# STM32MP25XXAK_Power.net
KiCad netlist of a schematic drawn in Altium Designer
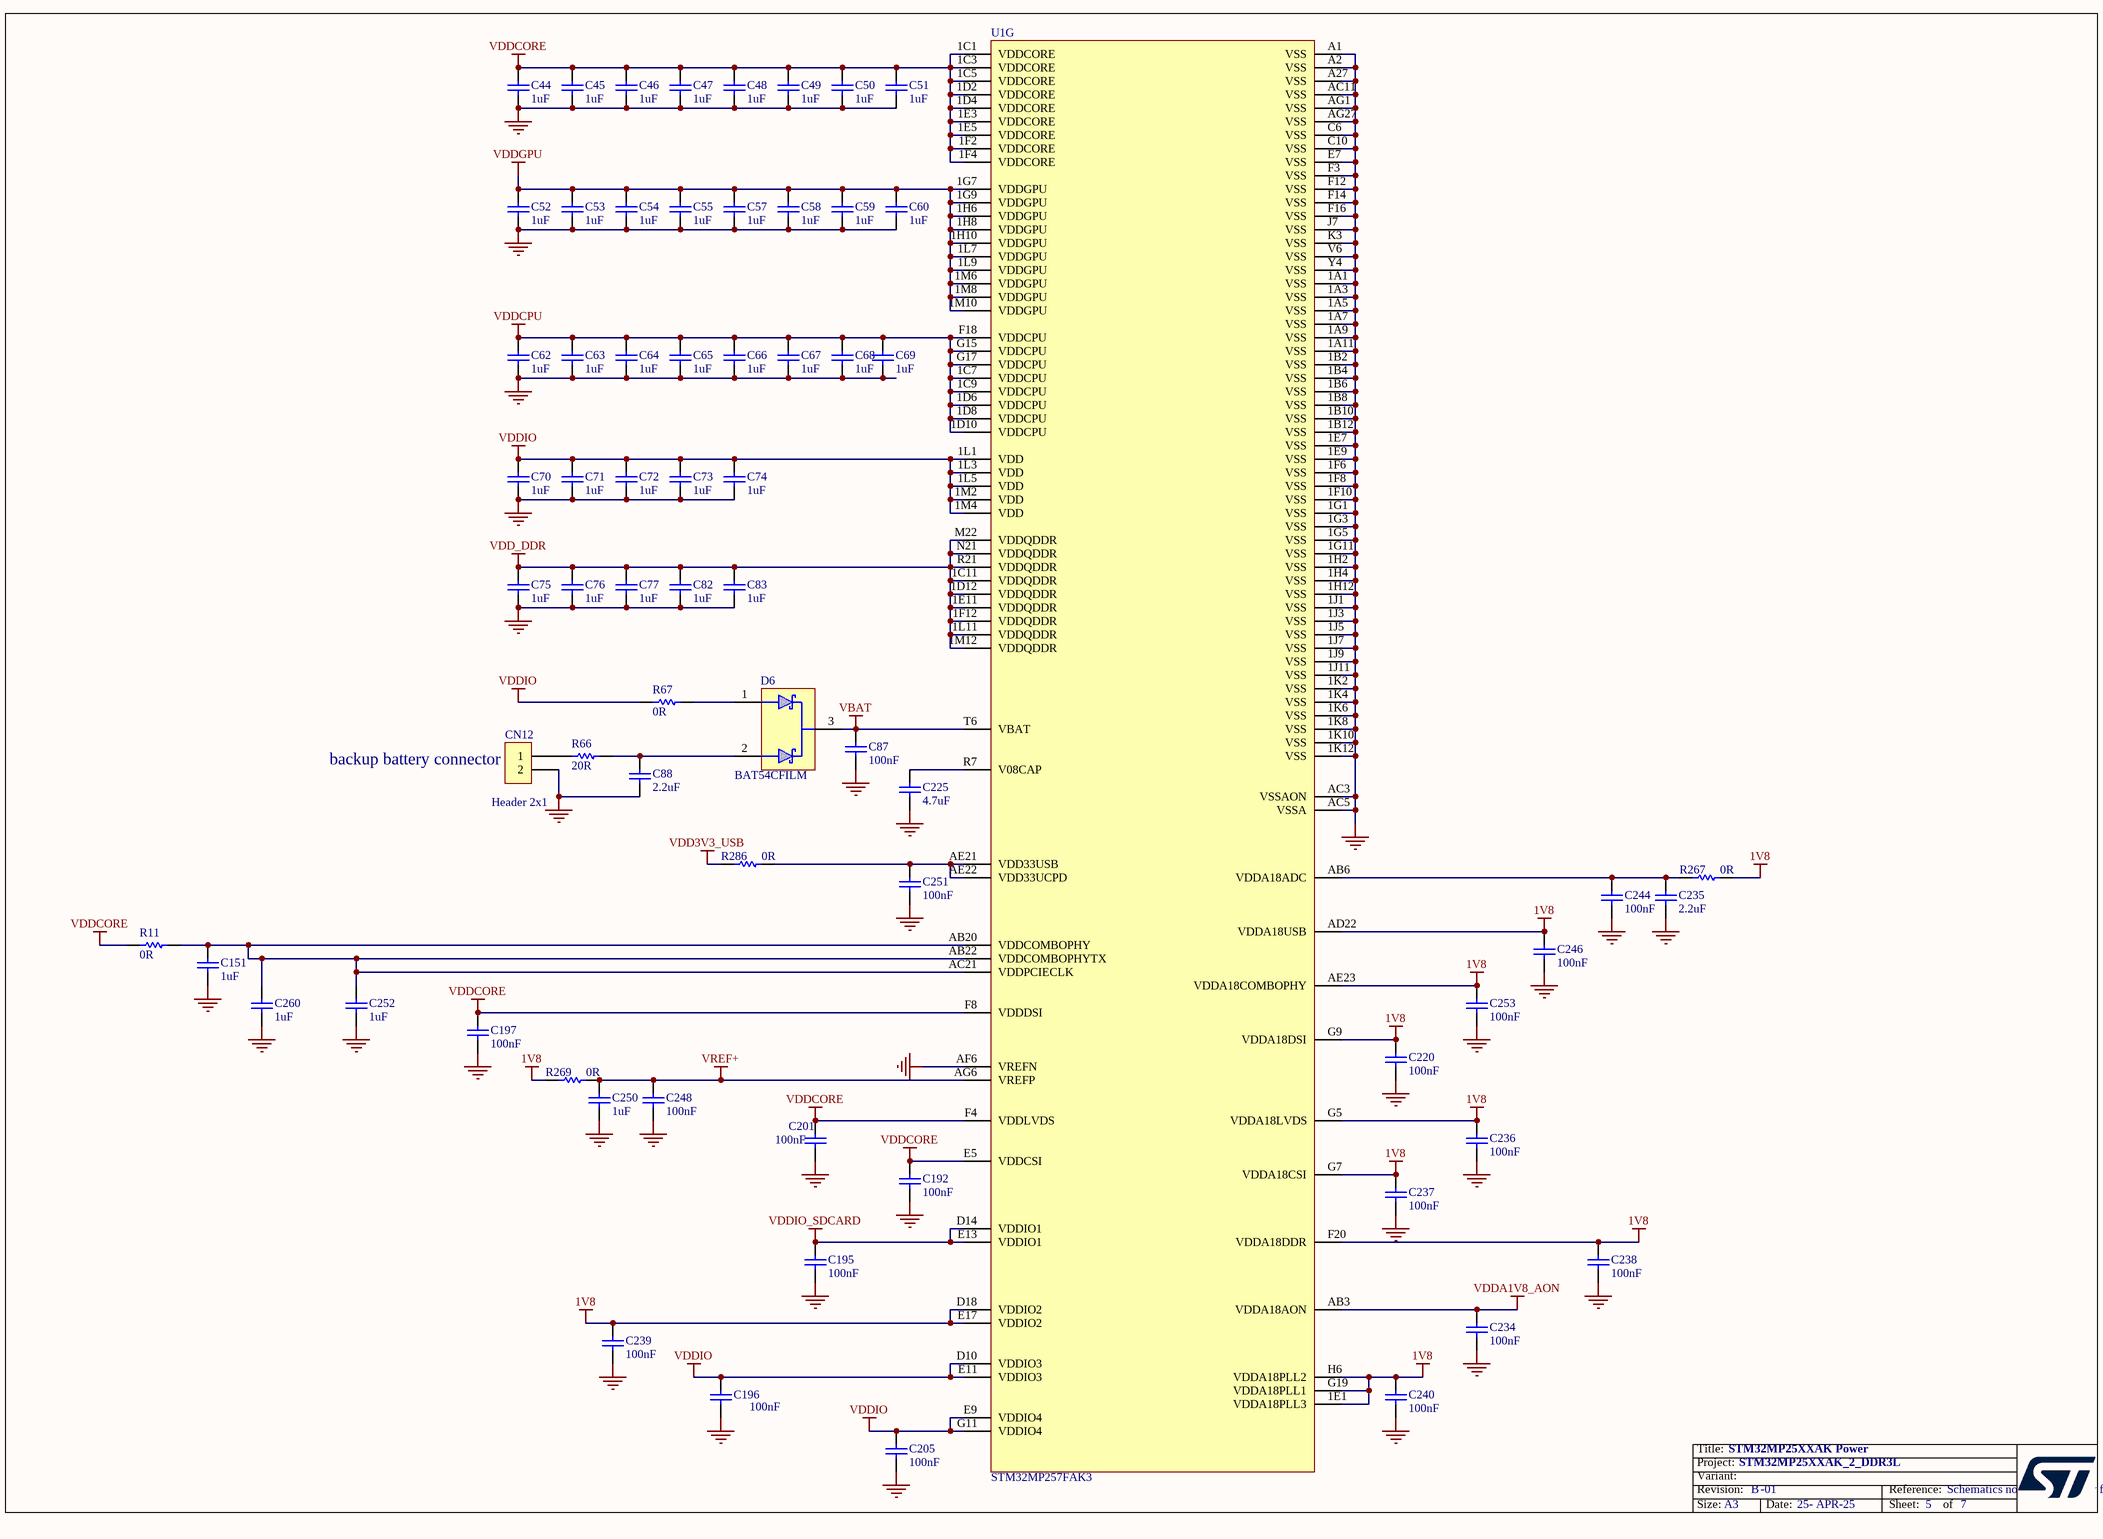
[diagram p0: STM32MP25XXAK Power.SchDoc]

(export (version "E")
  (design (tool "Eeschema 10.0.6"))
  (components
    (comp (ref "C44")
      (value "1uF")
      (footprint "C0201_MURATA_GRM033_H0P3")
      (description "Capacitor, MLCC, 1uF, 6.3V, X5R, +/-20%, 0201, T=0,3mm")
      (fields (field (name "INTERNAL_PART_NUMBER") "MCD-02377") (field (name "MANUFACTURER") "MURATA"))
      (libsource (lib "MCD_PARTS_database") (part "Capacitor"))
    )
    (comp (ref "C45")
      (value "1uF")
      (footprint "C0201_MURATA_GRM033_H0P3")
      (description "Capacitor, MLCC, 1uF, 6.3V, X5R, +/-20%, 0201, T=0,3mm")
      (fields (field (name "INTERNAL_PART_NUMBER") "MCD-02377") (field (name "MANUFACTURER") "MURATA"))
      (libsource (lib "MCD_PARTS_database") (part "Capacitor"))
    )
    (comp (ref "C46")
      (value "1uF")
      (footprint "C0201_MURATA_GRM033_H0P3")
      (description "Capacitor, MLCC, 1uF, 6.3V, X5R, +/-20%, 0201, T=0,3mm")
      (fields (field (name "INTERNAL_PART_NUMBER") "MCD-02377") (field (name "MANUFACTURER") "MURATA"))
      (libsource (lib "MCD_PARTS_database") (part "Capacitor"))
    )
    (comp (ref "C47")
      (value "1uF")
      (footprint "C0201_MURATA_GRM033_H0P3")
      (description "Capacitor, MLCC, 1uF, 6.3V, X5R, +/-20%, 0201, T=0,3mm")
      (fields (field (name "INTERNAL_PART_NUMBER") "MCD-02377") (field (name "MANUFACTURER") "MURATA"))
      (libsource (lib "MCD_PARTS_database") (part "Capacitor"))
    )
    (comp (ref "C48")
      (value "1uF")
      (footprint "C0201_MURATA_GRM033_H0P3")
      (description "Capacitor, MLCC, 1uF, 6.3V, X5R, +/-20%, 0201, T=0,3mm")
      (fields (field (name "INTERNAL_PART_NUMBER") "MCD-02377") (field (name "MANUFACTURER") "MURATA"))
      (libsource (lib "MCD_PARTS_database") (part "Capacitor"))
    )
    (comp (ref "C49")
      (value "1uF")
      (footprint "C0201_MURATA_GRM033_H0P3")
      (description "Capacitor, MLCC, 1uF, 6.3V, X5R, +/-20%, 0201, T=0,3mm")
      (fields (field (name "INTERNAL_PART_NUMBER") "MCD-02377") (field (name "MANUFACTURER") "MURATA"))
      (libsource (lib "MCD_PARTS_database") (part "Capacitor"))
    )
    (comp (ref "C50")
      (value "1uF")
      (footprint "C0201_MURATA_GRM033_H0P3")
      (description "Capacitor, MLCC, 1uF, 6.3V, X5R, +/-20%, 0201, T=0,3mm")
      (fields (field (name "INTERNAL_PART_NUMBER") "MCD-02377") (field (name "MANUFACTURER") "MURATA"))
      (libsource (lib "MCD_PARTS_database") (part "Capacitor"))
    )
    (comp (ref "C51")
      (value "1uF")
      (footprint "C0201_MURATA_GRM033_H0P3")
      (description "Capacitor, MLCC, 1uF, 6.3V, X5R, +/-20%, 0201, T=0,3mm")
      (fields (field (name "INTERNAL_PART_NUMBER") "MCD-02377") (field (name "MANUFACTURER") "MURATA"))
      (libsource (lib "MCD_PARTS_database") (part "Capacitor"))
    )
    (comp (ref "C52")
      (value "1uF")
      (footprint "C0201_MURATA_GRM033_H0P3")
      (description "Capacitor, MLCC, 1uF, 6.3V, X5R, +/-20%, 0201, T=0,3mm")
      (fields (field (name "INTERNAL_PART_NUMBER") "MCD-02377") (field (name "MANUFACTURER") "MURATA"))
      (libsource (lib "MCD_PARTS_database") (part "Capacitor"))
    )
    (comp (ref "C53")
      (value "1uF")
      (footprint "C0201_MURATA_GRM033_H0P3")
      (description "Capacitor, MLCC, 1uF, 6.3V, X5R, +/-20%, 0201, T=0,3mm")
      (fields (field (name "INTERNAL_PART_NUMBER") "MCD-02377") (field (name "MANUFACTURER") "MURATA"))
      (libsource (lib "MCD_PARTS_database") (part "Capacitor"))
    )
    (comp (ref "C54")
      (value "1uF")
      (footprint "C0201_MURATA_GRM033_H0P3")
      (description "Capacitor, MLCC, 1uF, 6.3V, X5R, +/-20%, 0201, T=0,3mm")
      (fields (field (name "INTERNAL_PART_NUMBER") "MCD-02377") (field (name "MANUFACTURER") "MURATA"))
      (libsource (lib "MCD_PARTS_database") (part "Capacitor"))
    )
    (comp (ref "C55")
      (value "1uF")
      (footprint "C0201_MURATA_GRM033_H0P3")
      (description "Capacitor, MLCC, 1uF, 6.3V, X5R, +/-20%, 0201, T=0,3mm")
      (fields (field (name "INTERNAL_PART_NUMBER") "MCD-02377") (field (name "MANUFACTURER") "MURATA"))
      (libsource (lib "MCD_PARTS_database") (part "Capacitor"))
    )
    (comp (ref "C57")
      (value "1uF")
      (footprint "C0201_MURATA_GRM033_H0P3")
      (description "Capacitor, MLCC, 1uF, 6.3V, X5R, +/-20%, 0201, T=0,3mm")
      (fields (field (name "INTERNAL_PART_NUMBER") "MCD-02377") (field (name "MANUFACTURER") "MURATA"))
      (libsource (lib "MCD_PARTS_database") (part "Capacitor"))
    )
    (comp (ref "C58")
      (value "1uF")
      (footprint "C0201_MURATA_GRM033_H0P3")
      (description "Capacitor, MLCC, 1uF, 6.3V, X5R, +/-20%, 0201, T=0,3mm")
      (fields (field (name "INTERNAL_PART_NUMBER") "MCD-02377") (field (name "MANUFACTURER") "MURATA"))
      (libsource (lib "MCD_PARTS_database") (part "Capacitor"))
    )
    (comp (ref "C59")
      (value "1uF")
      (footprint "C0201_MURATA_GRM033_H0P3")
      (description "Capacitor, MLCC, 1uF, 6.3V, X5R, +/-20%, 0201, T=0,3mm")
      (fields (field (name "INTERNAL_PART_NUMBER") "MCD-02377") (field (name "MANUFACTURER") "MURATA"))
      (libsource (lib "MCD_PARTS_database") (part "Capacitor"))
    )
    (comp (ref "C60")
      (value "1uF")
      (footprint "C0201_MURATA_GRM033_H0P3")
      (description "Capacitor, MLCC, 1uF, 6.3V, X5R, +/-20%, 0201, T=0,3mm")
      (fields (field (name "INTERNAL_PART_NUMBER") "MCD-02377") (field (name "MANUFACTURER") "MURATA"))
      (libsource (lib "MCD_PARTS_database") (part "Capacitor"))
    )
    (comp (ref "C62")
      (value "1uF")
      (footprint "C0201_MURATA_GRM033_H0P3")
      (description "Capacitor, MLCC, 1uF, 6.3V, X5R, +/-20%, 0201, T=0,3mm")
      (fields (field (name "INTERNAL_PART_NUMBER") "MCD-02377") (field (name "MANUFACTURER") "MURATA"))
      (libsource (lib "MCD_PARTS_database") (part "Capacitor"))
    )
    (comp (ref "C63")
      (value "1uF")
      (footprint "C0201_MURATA_GRM033_H0P3")
      (description "Capacitor, MLCC, 1uF, 6.3V, X5R, +/-20%, 0201, T=0,3mm")
      (fields (field (name "INTERNAL_PART_NUMBER") "MCD-02377") (field (name "MANUFACTURER") "MURATA"))
      (libsource (lib "MCD_PARTS_database") (part "Capacitor"))
    )
    (comp (ref "C64")
      (value "1uF")
      (footprint "C0201_MURATA_GRM033_H0P3")
      (description "Capacitor, MLCC, 1uF, 6.3V, X5R, +/-20%, 0201, T=0,3mm")
      (fields (field (name "INTERNAL_PART_NUMBER") "MCD-02377") (field (name "MANUFACTURER") "MURATA"))
      (libsource (lib "MCD_PARTS_database") (part "Capacitor"))
    )
    (comp (ref "C65")
      (value "1uF")
      (footprint "C0201_MURATA_GRM033_H0P3")
      (description "Capacitor, MLCC, 1uF, 6.3V, X5R, +/-20%, 0201, T=0,3mm")
      (fields (field (name "INTERNAL_PART_NUMBER") "MCD-02377") (field (name "MANUFACTURER") "MURATA"))
      (libsource (lib "MCD_PARTS_database") (part "Capacitor"))
    )
    (comp (ref "C66")
      (value "1uF")
      (footprint "C0201_MURATA_GRM033_H0P3")
      (description "Capacitor, MLCC, 1uF, 6.3V, X5R, +/-20%, 0201, T=0,3mm")
      (fields (field (name "INTERNAL_PART_NUMBER") "MCD-02377") (field (name "MANUFACTURER") "MURATA"))
      (libsource (lib "MCD_PARTS_database") (part "Capacitor"))
    )
    (comp (ref "C67")
      (value "1uF")
      (footprint "C0201_MURATA_GRM033_H0P3")
      (description "Capacitor, MLCC, 1uF, 6.3V, X5R, +/-20%, 0201, T=0,3mm")
      (fields (field (name "INTERNAL_PART_NUMBER") "MCD-02377") (field (name "MANUFACTURER") "MURATA"))
      (libsource (lib "MCD_PARTS_database") (part "Capacitor"))
    )
    (comp (ref "C68")
      (value "1uF")
      (footprint "C0201_MURATA_GRM033_H0P3")
      (description "Capacitor, MLCC, 1uF, 6.3V, X5R, +/-20%, 0201, T=0,3mm")
      (fields (field (name "INTERNAL_PART_NUMBER") "MCD-02377") (field (name "MANUFACTURER") "MURATA"))
      (libsource (lib "MCD_PARTS_database") (part "Capacitor"))
    )
    (comp (ref "C69")
      (value "1uF")
      (footprint "C0201_MURATA_GRM033_H0P3")
      (description "Capacitor, MLCC, 1uF, 6.3V, X5R, +/-20%, 0201, T=0,3mm")
      (fields (field (name "INTERNAL_PART_NUMBER") "MCD-02377") (field (name "MANUFACTURER") "MURATA"))
      (libsource (lib "MCD_PARTS_database") (part "Capacitor"))
    )
    (comp (ref "C70")
      (value "1uF")
      (footprint "C0201_MURATA_GRM033_H0P3")
      (description "Capacitor, MLCC, 1uF, 6.3V, X5R, +/-20%, 0201, T=0,3mm")
      (fields (field (name "INTERNAL_PART_NUMBER") "MCD-02377") (field (name "MANUFACTURER") "MURATA"))
      (libsource (lib "MCD_PARTS_database") (part "Capacitor"))
    )
    (comp (ref "C71")
      (value "1uF")
      (footprint "C0201_MURATA_GRM033_H0P3")
      (description "Capacitor, MLCC, 1uF, 6.3V, X5R, +/-20%, 0201, T=0,3mm")
      (fields (field (name "INTERNAL_PART_NUMBER") "MCD-02377") (field (name "MANUFACTURER") "MURATA"))
      (libsource (lib "MCD_PARTS_database") (part "Capacitor"))
    )
    (comp (ref "C72")
      (value "1uF")
      (footprint "C0201_MURATA_GRM033_H0P3")
      (description "Capacitor, MLCC, 1uF, 6.3V, X5R, +/-20%, 0201, T=0,3mm")
      (fields (field (name "INTERNAL_PART_NUMBER") "MCD-02377") (field (name "MANUFACTURER") "MURATA"))
      (libsource (lib "MCD_PARTS_database") (part "Capacitor"))
    )
    (comp (ref "C73")
      (value "1uF")
      (footprint "C0201_MURATA_GRM033_H0P3")
      (description "Capacitor, MLCC, 1uF, 6.3V, X5R, +/-20%, 0201, T=0,3mm")
      (fields (field (name "INTERNAL_PART_NUMBER") "MCD-02377") (field (name "MANUFACTURER") "MURATA"))
      (libsource (lib "MCD_PARTS_database") (part "Capacitor"))
    )
    (comp (ref "C74")
      (value "1uF")
      (footprint "C0201_MURATA_GRM033_H0P3")
      (description "Capacitor, MLCC, 1uF, 6.3V, X5R, +/-20%, 0201, T=0,3mm")
      (fields (field (name "INTERNAL_PART_NUMBER") "MCD-02377") (field (name "MANUFACTURER") "MURATA"))
      (libsource (lib "MCD_PARTS_database") (part "Capacitor"))
    )
    (comp (ref "C75")
      (value "1uF")
      (footprint "C0201_MURATA_GRM033_H0P3")
      (description "Capacitor, MLCC, 1uF, 6.3V, X5R, +/-20%, 0201, T=0,3mm")
      (fields (field (name "INTERNAL_PART_NUMBER") "MCD-02377") (field (name "MANUFACTURER") "MURATA"))
      (libsource (lib "MCD_PARTS_database") (part "Capacitor"))
    )
    (comp (ref "C76")
      (value "1uF")
      (footprint "C0201_MURATA_GRM033_H0P3")
      (description "Capacitor, MLCC, 1uF, 6.3V, X5R, +/-20%, 0201, T=0,3mm")
      (fields (field (name "INTERNAL_PART_NUMBER") "MCD-02377") (field (name "MANUFACTURER") "MURATA"))
      (libsource (lib "MCD_PARTS_database") (part "Capacitor"))
    )
    (comp (ref "C77")
      (value "1uF")
      (footprint "C0201_MURATA_GRM033_H0P3")
      (description "Capacitor, MLCC, 1uF, 6.3V, X5R, +/-20%, 0201, T=0,3mm")
      (fields (field (name "INTERNAL_PART_NUMBER") "MCD-02377") (field (name "MANUFACTURER") "MURATA"))
      (libsource (lib "MCD_PARTS_database") (part "Capacitor"))
    )
    (comp (ref "C82")
      (value "1uF")
      (footprint "C0201_MURATA_GRM033_H0P3")
      (description "Capacitor, MLCC, 1uF, 6.3V, X5R, +/-20%, 0201, T=0,3mm")
      (fields (field (name "INTERNAL_PART_NUMBER") "MCD-02377") (field (name "MANUFACTURER") "MURATA"))
      (libsource (lib "MCD_PARTS_database") (part "Capacitor"))
    )
    (comp (ref "C83")
      (value "1uF")
      (footprint "C0201_MURATA_GRM033_H0P3")
      (description "Capacitor, MLCC, 1uF, 6.3V, X5R, +/-20%, 0201, T=0,3mm")
      (fields (field (name "INTERNAL_PART_NUMBER") "MCD-02377") (field (name "MANUFACTURER") "MURATA"))
      (libsource (lib "MCD_PARTS_database") (part "Capacitor"))
    )
    (comp (ref "C87")
      (value "100nF")
      (footprint "C0402")
      (description "Capacitor,100nF,16V,X7R,10%,0402")
      (fields
        (field (name "INTERNAL_PART_NUMBER") "MCD-00006")
        (field (name "MANUFACTURER_PART_NUMBER") "CC0402KRX7R7BB104")
        (field (name "PROVIDED_BY") "SUBCO")
      )
      (libsource (lib "MCD_PARTS_database") (part "Capacitor"))
    )
    (comp (ref "C88")
      (value "2.2uF")
      (footprint "C0402")
      (description "Capacitor, MLCC, 2.2uF, 6V3, X5R,+/-10%, 0402, T=0.5mm")
      (fields (field (name "INTERNAL_PART_NUMBER") "MCD-01823") (field (name "MANUFACTURER") "MURATA"))
      (libsource (lib "MCD_PARTS_database") (part "Capacitor"))
    )
    (comp (ref "C151")
      (value "1uF")
      (footprint "C0201_MURATA_GRM033_H0P3")
      (description "Capacitor, MLCC, 1uF, 6.3V, X5R, +/-20%, 0201, T=0,3mm")
      (fields
        (field (name "INTERNAL_PART_NUMBER") "MCD-02377")
        (field (name "MANUFACTURER_PART_NUMBER") "GRM033R60J105MEA2")
      )
      (libsource (lib "MCD_PARTS_database") (part "Capacitor"))
    )
    (comp (ref "C192")
      (value "100nF")
      (footprint "C0201_MURATA_GRM033_H0P3")
      (description "Capacitor, MLCC,100nF, 10V, X7R, +/-10%, 0201, T=0.3mm")
      (fields (field (name "INTERNAL_PART_NUMBER") "MCD-01535") (field (name "MANUFACTURER") "MURATA"))
      (libsource (lib "MCD_PARTS_database") (part "Capacitor"))
    )
    (comp (ref "C195")
      (value "100nF")
      (footprint "C0201_MURATA_GRM033_H0P3")
      (description "Capacitor, MLCC,100nF, 10V, X7R, +/-10%, 0201, T=0.3mm")
      (fields (field (name "INTERNAL_PART_NUMBER") "MCD-01535") (field (name "MANUFACTURER") "MURATA"))
      (libsource (lib "MCD_PARTS_database") (part "Capacitor"))
    )
    (comp (ref "C196")
      (value "100nF")
      (footprint "C0201_MURATA_GRM033_H0P3")
      (description "Capacitor, MLCC,100nF, 10V, X7R, +/-10%, 0201, T=0.3mm")
      (fields (field (name "INTERNAL_PART_NUMBER") "MCD-01535") (field (name "MANUFACTURER") "MURATA"))
      (libsource (lib "MCD_PARTS_database") (part "Capacitor"))
    )
    (comp (ref "C197")
      (value "100nF")
      (footprint "C0201_MURATA_GRM033_H0P3")
      (description "Capacitor, MLCC,100nF, 10V, X7R, +/-10%, 0201, T=0.3mm")
      (fields (field (name "INTERNAL_PART_NUMBER") "MCD-01535") (field (name "MANUFACTURER") "MURATA"))
      (libsource (lib "MCD_PARTS_database") (part "Capacitor"))
    )
    (comp (ref "C201")
      (value "100nF")
      (footprint "C0201_MURATA_GRM033_H0P3")
      (description "Capacitor, MLCC,100nF, 10V, X7R, +/-10%, 0201, T=0.3mm")
      (fields (field (name "INTERNAL_PART_NUMBER") "MCD-01535") (field (name "MANUFACTURER") "MURATA"))
      (libsource (lib "MCD_PARTS_database") (part "Capacitor"))
    )
    (comp (ref "C205")
      (value "100nF")
      (footprint "C0201_MURATA_GRM033_H0P3")
      (description "Capacitor, MLCC,100nF, 10V, X7R, +/-10%, 0201, T=0.3mm")
      (fields (field (name "INTERNAL_PART_NUMBER") "MCD-01535") (field (name "MANUFACTURER") "MURATA"))
      (libsource (lib "MCD_PARTS_database") (part "Capacitor"))
    )
    (comp (ref "C220")
      (value "100nF")
      (footprint "C0201_MURATA_GRM033_H0P3")
      (description "Capacitor, MLCC,100nF, 10V, X7R, +/-10%, 0201, T=0.3mm")
      (fields (field (name "INTERNAL_PART_NUMBER") "MCD-01535") (field (name "MANUFACTURER") "MURATA"))
      (libsource (lib "MCD_PARTS_database") (part "Capacitor"))
    )
    (comp (ref "C225")
      (value "4.7uF")
      (footprint "C0201_H0P5")
      (description "Capacitor, MLCC, 4,7uF, 6V3, X5R, +/-20%, 0201, T=0.5mm")
      (fields (field (name "INTERNAL_PART_NUMBER") "MCD-01534") (field (name "MANUFACTURER") "MURATA"))
      (libsource (lib "MCD_PARTS_database") (part "Capacitor"))
    )
    (comp (ref "C234")
      (value "100nF")
      (footprint "C0201_MURATA_GRM033_H0P3")
      (description "Capacitor, MLCC,100nF, 10V, X7R, +/-10%, 0201, T=0.3mm")
      (fields (field (name "INTERNAL_PART_NUMBER") "MCD-01535") (field (name "MANUFACTURER") "MURATA"))
      (libsource (lib "MCD_PARTS_database") (part "Capacitor"))
    )
    (comp (ref "C235")
      (value "2.2uF")
      (footprint "C0201_H0P5")
      (description "Capacitor, MLCC, 2.2uF, 10V, X5R,+/-10%, 0201, T=0.5mm")
      (fields (field (name "INTERNAL_PART_NUMBER") "MCD-02235") (field (name "MANUFACTURER") "MURATA"))
      (libsource (lib "MCD_PARTS_database") (part "Capacitor"))
    )
    (comp (ref "C236")
      (value "100nF")
      (footprint "C0201_MURATA_GRM033_H0P3")
      (description "Capacitor, MLCC,100nF, 10V, X7R, +/-10%, 0201, T=0.3mm")
      (fields (field (name "INTERNAL_PART_NUMBER") "MCD-01535") (field (name "MANUFACTURER") "MURATA"))
      (libsource (lib "MCD_PARTS_database") (part "Capacitor"))
    )
    (comp (ref "C237")
      (value "100nF")
      (footprint "C0201_MURATA_GRM033_H0P3")
      (description "Capacitor, MLCC,100nF, 10V, X7R, +/-10%, 0201, T=0.3mm")
      (fields (field (name "INTERNAL_PART_NUMBER") "MCD-01535") (field (name "MANUFACTURER") "MURATA"))
      (libsource (lib "MCD_PARTS_database") (part "Capacitor"))
    )
    (comp (ref "C238")
      (value "100nF")
      (footprint "C0201_MURATA_GRM033_H0P3")
      (description "Capacitor, MLCC,100nF, 10V, X7R, +/-10%, 0201, T=0.3mm")
      (fields (field (name "INTERNAL_PART_NUMBER") "MCD-01535") (field (name "MANUFACTURER") "MURATA"))
      (libsource (lib "MCD_PARTS_database") (part "Capacitor"))
    )
    (comp (ref "C239")
      (value "100nF")
      (footprint "C0201_MURATA_GRM033_H0P3")
      (description "Capacitor, MLCC,100nF, 10V, X7R, +/-10%, 0201, T=0.3mm")
      (fields (field (name "INTERNAL_PART_NUMBER") "MCD-01535") (field (name "MANUFACTURER") "MURATA"))
      (libsource (lib "MCD_PARTS_database") (part "Capacitor"))
    )
    (comp (ref "C240")
      (value "100nF")
      (footprint "C0201_MURATA_GRM033_H0P3")
      (description "Capacitor, MLCC,100nF, 10V, X7R, +/-10%, 0201, T=0.3mm")
      (fields (field (name "INTERNAL_PART_NUMBER") "MCD-01535") (field (name "MANUFACTURER") "MURATA"))
      (libsource (lib "MCD_PARTS_database") (part "Capacitor"))
    )
    (comp (ref "C244")
      (value "100nF")
      (footprint "C0201_MURATA_GRM033_H0P3")
      (description "Capacitor, MLCC,100nF, 10V, X7R, +/-10%, 0201, T=0.3mm")
      (fields (field (name "INTERNAL_PART_NUMBER") "MCD-01535") (field (name "MANUFACTURER") "MURATA"))
      (libsource (lib "MCD_PARTS_database") (part "Capacitor"))
    )
    (comp (ref "C246")
      (value "100nF")
      (footprint "C0201_MURATA_GRM033_H0P3")
      (description "Capacitor, MLCC,100nF, 10V, X7R, +/-10%, 0201, T=0.3mm")
      (fields (field (name "INTERNAL_PART_NUMBER") "MCD-01535") (field (name "MANUFACTURER") "MURATA"))
      (libsource (lib "MCD_PARTS_database") (part "Capacitor"))
    )
    (comp (ref "C248")
      (value "100nF")
      (footprint "C0201_MURATA_GRM033_H0P3")
      (description "Capacitor, MLCC,100nF, 10V, X7R, +/-10%, 0201, T=0.3mm")
      (fields (field (name "INTERNAL_PART_NUMBER") "MCD-01535") (field (name "MANUFACTURER") "MURATA"))
      (libsource (lib "MCD_PARTS_database") (part "Capacitor"))
    )
    (comp (ref "C250")
      (value "1uF")
      (footprint "C0201_MURATA_GRM033_H0P3")
      (description "Capacitor, MLCC, 1uF, 6.3V, X5R, +/-20%, 0201, T=0,3mm")
      (fields
        (field (name "INTERNAL_PART_NUMBER") "MCD-02377")
        (field (name "MANUFACTURER_PART_NUMBER") "GRM033R60J105MEA2")
      )
      (libsource (lib "MCD_PARTS_database") (part "Capacitor"))
    )
    (comp (ref "C251")
      (value "100nF")
      (footprint "C0201_MURATA_GRM033_H0P3")
      (description "Capacitor, MLCC,100nF, 10V, X7R, +/-10%, 0201, T=0.3mm")
      (fields (field (name "INTERNAL_PART_NUMBER") "MCD-01535") (field (name "MANUFACTURER") "MURATA"))
      (libsource (lib "MCD_PARTS_database") (part "Capacitor"))
    )
    (comp (ref "C252")
      (value "1uF")
      (footprint "C0201_MURATA_GRM033_H0P3")
      (description "Capacitor, MLCC, 1uF, 6.3V, X5R, +/-20%, 0201, T=0,3mm")
      (fields
        (field (name "INTERNAL_PART_NUMBER") "MCD-02377")
        (field (name "MANUFACTURER_PART_NUMBER") "GRM033R60J105MEA2")
      )
      (libsource (lib "MCD_PARTS_database") (part "Capacitor"))
    )
    (comp (ref "C253")
      (value "100nF")
      (footprint "C0201_MURATA_GRM033_H0P3")
      (description "Capacitor, MLCC,100nF, 10V, X7R, +/-10%, 0201, T=0.3mm")
      (fields (field (name "INTERNAL_PART_NUMBER") "MCD-01535") (field (name "MANUFACTURER") "MURATA"))
      (libsource (lib "MCD_PARTS_database") (part "Capacitor"))
    )
    (comp (ref "C260")
      (value "1uF")
      (footprint "C0201_MURATA_GRM033_H0P3")
      (description "Capacitor, MLCC, 1uF, 6.3V, X5R, +/-20%, 0201, T=0,3mm")
      (fields
        (field (name "INTERNAL_PART_NUMBER") "MCD-02377")
        (field (name "MANUFACTURER_PART_NUMBER") "GRM033R60J105MEA2")
      )
      (libsource (lib "MCD_PARTS_database") (part "Capacitor"))
    )
    (comp (ref "CN12")
      (value "Header 2x1")
      (footprint "CON_MOLEX_53047-0210")
      (description "Header 2 circuits, 1.25mm Pitch ,  Vertical, with Friction Lock")
      (fields
        (field (name "INTERNAL_PART_NUMBER") "MCD-00655")
        (field (name "MANUFACTURER_PART_NUMBER") "53047-0210")
        (field (name "PROVIDED_BY") "SUBCO")
      )
      (libsource (lib "MCD_PARTS_database") (part "Header 2x1"))
    )
    (comp (ref "D6")
      (value "BAT54CFILM")
      (footprint "DIO_SOT23")
      (description "Diode, Schottky, Dual Common Cathode, 0V3, 300mA, 40V, SOT-23")
      (fields
        (field (name "INTERNAL_PART_NUMBER") "MCD-03280")
        (field (name "MANUFACTURER") "STMICROELECTRONICS")
      )
      (libsource (lib "MCD_PARTS_database") (part "DIODE_3P_DUAL_COMMON_CATHODE"))
    )
    (comp (ref "R11")
      (value "0R")
      (footprint "R0603")
      (description "Resistor, 0R, 0603, +/-5%, 1/10W")
      (fields (field (name "INTERNAL_PART_NUMBER") "MCD-00056") (field (name "MANUFACTURER") "YAGEO"))
      (libsource (lib "MCD_PARTS_database") (part "Resistor"))
    )
    (comp (ref "R66")
      (value "20R")
      (footprint "R0402")
      (description "Resistor, 20R, 0402, +/-1%, 1/16W")
      (fields (field (name "INTERNAL_PART_NUMBER") "MCD-00058") (field (name "BMS_PART_NUMBER") "9131027"))
      (libsource (lib "MCD_PARTS_database") (part "Resistor"))
    )
    (comp (ref "R67")
      (value "0R")
      (footprint "R0402")
      (description "Resistor, 0R, 0402, +/-5%, 1/16W")
      (fields
        (field (name "INTERNAL_PART_NUMBER") "MCD-00052")
        (field (name "MANUFACTURER_PART_NUMBER") "RC0402JR-070RL")
      )
      (libsource (lib "MCD_PARTS_database") (part "Resistor"))
    )
    (comp (ref "R267")
      (value "0R")
      (footprint "R0402")
      (description "Resistor,0R,0402,5%,1/16W")
      (fields
        (field (name "INTERNAL_PART_NUMBER") "MCD-00052")
        (field (name "MANUFACTURER_PART_NUMBER") "RC0402JR-070RL")
        (field (name "PROVIDED_BY") "SUBCO")
      )
      (libsource (lib "MCD_PARTS_database") (part "Resistor"))
    )
    (comp (ref "R269")
      (value "0R")
      (footprint "R0402")
      (description "Resistor,0R,0402,5%,1/16W")
      (fields
        (field (name "INTERNAL_PART_NUMBER") "MCD-00052")
        (field (name "MANUFACTURER_PART_NUMBER") "RC0402JR-070RL")
        (field (name "PROVIDED_BY") "SUBCO")
      )
      (libsource (lib "MCD_PARTS_database") (part "Resistor"))
    )
    (comp (ref "R286")
      (value "0R")
      (footprint "R0402")
      (description "Resistor,0R,0402,5%,1/16W")
      (fields
        (field (name "INTERNAL_PART_NUMBER") "MCD-00052")
        (field (name "MANUFACTURER_PART_NUMBER") "RC0402JR-070RL")
        (field (name "PROVIDED_BY") "SUBCO")
      )
      (libsource (lib "MCD_PARTS_database") (part "Resistor"))
    )
    (comp (ref "U1")
      (value "STM32MP257FAK3")
      (footprint "ICC_TFBGA424_14X14_P050_H1P20_CODE-B0A2")
      (description "MPU , 2xCortex-A35@1.5GHz, Cortex-M33@400MHz, TFBGA 14x14, pitch 0.5, 648KB SRAM, With Crypto")
      (fields
        (field (name "INTERNAL_PART_NUMBER") "MCD-03375")
        (field (name "MANUFACTURER") "STMICROELECTRONICS")
      )
      (libsource (lib "MCD_PARTS_database") (part "STM32MP257FAK3"))
    )
  )
  (nets
    (net (code "1") (name "1V8") (class "Default")
      (node (ref "C220") (pin "2") (pinfunction "2_2") (pintype "passive"))
      (node (ref "C236") (pin "2") (pinfunction "2_2") (pintype "passive"))
      (node (ref "C237") (pin "2") (pinfunction "2_2") (pintype "passive"))
      (node (ref "C238") (pin "2") (pinfunction "2_2") (pintype "passive"))
      (node (ref "C239") (pin "2") (pinfunction "2_2") (pintype "passive"))
      (node (ref "C240") (pin "2") (pinfunction "2_2") (pintype "passive"))
      (node (ref "C246") (pin "2") (pinfunction "2_2") (pintype "passive"))
      (node (ref "C253") (pin "2") (pinfunction "2_2") (pintype "passive"))
      (node (ref "R267") (pin "2") (pinfunction "2_2") (pintype "passive"))
      (node (ref "R269") (pin "1") (pinfunction "1_1") (pintype "passive"))
      (node (ref "U1") (pin "1E1") (pinfunction "VDDA18PLL3_1E1") (pintype "passive"))
      (node (ref "U1") (pin "AD22") (pinfunction "VDDA18USB_AD22") (pintype "passive"))
      (node (ref "U1") (pin "AE23") (pinfunction "VDDA18COMBOPHY_AE23") (pintype "passive"))
      (node (ref "U1") (pin "D18") (pinfunction "VDDIO2_D18") (pintype "passive"))
      (node (ref "U1") (pin "E17") (pinfunction "VDDIO2_E17") (pintype "passive"))
      (node (ref "U1") (pin "F20") (pinfunction "VDDA18DDR_F20") (pintype "passive"))
      (node (ref "U1") (pin "G19") (pinfunction "VDDA18PLL1_G19") (pintype "passive"))
      (node (ref "U1") (pin "G5") (pinfunction "VDDA18LVDS_G5") (pintype "passive"))
      (node (ref "U1") (pin "G7") (pinfunction "VDDA18CSI_G7") (pintype "passive"))
      (node (ref "U1") (pin "G9") (pinfunction "VDDA18DSI_G9") (pintype "passive"))
      (node (ref "U1") (pin "H6") (pinfunction "VDDA18PLL2_H6") (pintype "passive"))
    )
    (net (code "2") (name "GND") (class "Default")
      (node (ref "C151") (pin "1") (pinfunction "1_1") (pintype "passive"))
      (node (ref "C192") (pin "1") (pinfunction "1_1") (pintype "passive"))
      (node (ref "C195") (pin "1") (pinfunction "1_1") (pintype "passive"))
      (node (ref "C196") (pin "1") (pinfunction "1_1") (pintype "passive"))
      (node (ref "C197") (pin "1") (pinfunction "1_1") (pintype "passive"))
      (node (ref "C201") (pin "1") (pinfunction "1_1") (pintype "passive"))
      (node (ref "C205") (pin "1") (pinfunction "1_1") (pintype "passive"))
      (node (ref "C220") (pin "1") (pinfunction "1_1") (pintype "passive"))
      (node (ref "C225") (pin "1") (pinfunction "1_1") (pintype "passive"))
      (node (ref "C234") (pin "1") (pinfunction "1_1") (pintype "passive"))
      (node (ref "C235") (pin "1") (pinfunction "1_1") (pintype "passive"))
      (node (ref "C236") (pin "1") (pinfunction "1_1") (pintype "passive"))
      (node (ref "C237") (pin "1") (pinfunction "1_1") (pintype "passive"))
      (node (ref "C238") (pin "1") (pinfunction "1_1") (pintype "passive"))
      (node (ref "C239") (pin "1") (pinfunction "1_1") (pintype "passive"))
      (node (ref "C240") (pin "1") (pinfunction "1_1") (pintype "passive"))
      (node (ref "C244") (pin "1") (pinfunction "1_1") (pintype "passive"))
      (node (ref "C246") (pin "1") (pinfunction "1_1") (pintype "passive"))
      (node (ref "C248") (pin "1") (pinfunction "1_1") (pintype "passive"))
      (node (ref "C250") (pin "1") (pinfunction "1_1") (pintype "passive"))
      (node (ref "C251") (pin "1") (pinfunction "1_1") (pintype "passive"))
      (node (ref "C252") (pin "1") (pinfunction "1_1") (pintype "passive"))
      (node (ref "C253") (pin "1") (pinfunction "1_1") (pintype "passive"))
      (node (ref "C260") (pin "1") (pinfunction "1_1") (pintype "passive"))
      (node (ref "C44") (pin "2") (pinfunction "2_2") (pintype "passive"))
      (node (ref "C45") (pin "1") (pinfunction "1_1") (pintype "passive"))
      (node (ref "C46") (pin "1") (pinfunction "1_1") (pintype "passive"))
      (node (ref "C47") (pin "2") (pinfunction "2_2") (pintype "passive"))
      (node (ref "C48") (pin "1") (pinfunction "1_1") (pintype "passive"))
      (node (ref "C49") (pin "1") (pinfunction "1_1") (pintype "passive"))
      (node (ref "C50") (pin "1") (pinfunction "1_1") (pintype "passive"))
      (node (ref "C51") (pin "1") (pinfunction "1_1") (pintype "passive"))
      (node (ref "C52") (pin "1") (pinfunction "1_1") (pintype "passive"))
      (node (ref "C53") (pin "1") (pinfunction "1_1") (pintype "passive"))
      (node (ref "C54") (pin "1") (pinfunction "1_1") (pintype "passive"))
      (node (ref "C55") (pin "1") (pinfunction "1_1") (pintype "passive"))
      (node (ref "C57") (pin "1") (pinfunction "1_1") (pintype "passive"))
      (node (ref "C58") (pin "1") (pinfunction "1_1") (pintype "passive"))
      (node (ref "C59") (pin "1") (pinfunction "1_1") (pintype "passive"))
      (node (ref "C60") (pin "1") (pinfunction "1_1") (pintype "passive"))
      (node (ref "C62") (pin "2") (pinfunction "2_2") (pintype "passive"))
      (node (ref "C63") (pin "1") (pinfunction "1_1") (pintype "passive"))
      (node (ref "C64") (pin "1") (pinfunction "1_1") (pintype "passive"))
      (node (ref "C65") (pin "2") (pinfunction "2_2") (pintype "passive"))
      (node (ref "C66") (pin "1") (pinfunction "1_1") (pintype "passive"))
      (node (ref "C67") (pin "1") (pinfunction "1_1") (pintype "passive"))
      (node (ref "C68") (pin "1") (pinfunction "1_1") (pintype "passive"))
      (node (ref "C69") (pin "1") (pinfunction "1_1") (pintype "passive"))
      (node (ref "C70") (pin "2") (pinfunction "2_2") (pintype "passive"))
      (node (ref "C71") (pin "1") (pinfunction "1_1") (pintype "passive"))
      (node (ref "C72") (pin "1") (pinfunction "1_1") (pintype "passive"))
      (node (ref "C73") (pin "2") (pinfunction "2_2") (pintype "passive"))
      (node (ref "C74") (pin "1") (pinfunction "1_1") (pintype "passive"))
      (node (ref "C75") (pin "1") (pinfunction "1_1") (pintype "passive"))
      (node (ref "C76") (pin "1") (pinfunction "1_1") (pintype "passive"))
      (node (ref "C77") (pin "2") (pinfunction "2_2") (pintype "passive"))
      (node (ref "C82") (pin "1") (pinfunction "1_1") (pintype "passive"))
      (node (ref "C83") (pin "1") (pinfunction "1_1") (pintype "passive"))
      (node (ref "C87") (pin "1") (pinfunction "1_1") (pintype "passive"))
      (node (ref "C88") (pin "1") (pinfunction "1_1") (pintype "passive"))
      (node (ref "CN12") (pin "2") (pinfunction "2_2") (pintype "passive"))
      (node (ref "U1") (pin "1A1") (pinfunction "VSS_1A1") (pintype "passive"))
      (node (ref "U1") (pin "1A11") (pinfunction "VSS_1A11") (pintype "passive"))
      (node (ref "U1") (pin "1A3") (pinfunction "VSS_1A3") (pintype "passive"))
      (node (ref "U1") (pin "1A5") (pinfunction "VSS_1A5") (pintype "passive"))
      (node (ref "U1") (pin "1A7") (pinfunction "VSS_1A7") (pintype "passive"))
      (node (ref "U1") (pin "1A9") (pinfunction "VSS_1A9") (pintype "passive"))
      (node (ref "U1") (pin "1B10") (pinfunction "VSS_1B10") (pintype "passive"))
      (node (ref "U1") (pin "1B12") (pinfunction "VSS_1B12") (pintype "passive"))
      (node (ref "U1") (pin "1B2") (pinfunction "VSS_1B2") (pintype "passive"))
      (node (ref "U1") (pin "1B4") (pinfunction "VSS_1B4") (pintype "passive"))
      (node (ref "U1") (pin "1B6") (pinfunction "VSS_1B6") (pintype "passive"))
      (node (ref "U1") (pin "1B8") (pinfunction "VSS_1B8") (pintype "passive"))
      (node (ref "U1") (pin "1E7") (pinfunction "VSS_1E7") (pintype "passive"))
      (node (ref "U1") (pin "1E9") (pinfunction "VSS_1E9") (pintype "passive"))
      (node (ref "U1") (pin "1F10") (pinfunction "VSS_1F10") (pintype "passive"))
      (node (ref "U1") (pin "1F6") (pinfunction "VSS_1F6") (pintype "passive"))
      (node (ref "U1") (pin "1F8") (pinfunction "VSS_1F8") (pintype "passive"))
      (node (ref "U1") (pin "1G1") (pinfunction "VSS_1G1") (pintype "passive"))
      (node (ref "U1") (pin "1G11") (pinfunction "VSS_1G11") (pintype "passive"))
      (node (ref "U1") (pin "1G3") (pinfunction "VSS_1G3") (pintype "passive"))
      (node (ref "U1") (pin "1G5") (pinfunction "VSS_1G5") (pintype "passive"))
      (node (ref "U1") (pin "1H12") (pinfunction "VSS_1H12") (pintype "passive"))
      (node (ref "U1") (pin "1H2") (pinfunction "VSS_1H2") (pintype "passive"))
      (node (ref "U1") (pin "1H4") (pinfunction "VSS_1H4") (pintype "passive"))
      (node (ref "U1") (pin "1J1") (pinfunction "VSS_1J1") (pintype "passive"))
      (node (ref "U1") (pin "1J11") (pinfunction "VSS_1J11") (pintype "passive"))
      (node (ref "U1") (pin "1J3") (pinfunction "VSS_1J3") (pintype "passive"))
      (node (ref "U1") (pin "1J5") (pinfunction "VSS_1J5") (pintype "passive"))
      (node (ref "U1") (pin "1J7") (pinfunction "VSS_1J7") (pintype "passive"))
      (node (ref "U1") (pin "1J9") (pinfunction "VSS_1J9") (pintype "passive"))
      (node (ref "U1") (pin "1K10") (pinfunction "VSS_1K10") (pintype "passive"))
      (node (ref "U1") (pin "1K12") (pinfunction "VSS_1K12") (pintype "passive"))
      (node (ref "U1") (pin "1K2") (pinfunction "VSS_1K2") (pintype "passive"))
      (node (ref "U1") (pin "1K4") (pinfunction "VSS_1K4") (pintype "passive"))
      (node (ref "U1") (pin "1K6") (pinfunction "VSS_1K6") (pintype "passive"))
      (node (ref "U1") (pin "1K8") (pinfunction "VSS_1K8") (pintype "passive"))
      (node (ref "U1") (pin "A1") (pinfunction "VSS_A1") (pintype "passive"))
      (node (ref "U1") (pin "A2") (pinfunction "VSS_A2") (pintype "passive"))
      (node (ref "U1") (pin "A27") (pinfunction "VSS_A27") (pintype "passive"))
      (node (ref "U1") (pin "AC11") (pinfunction "VSS_AC11") (pintype "passive"))
      (node (ref "U1") (pin "AC3") (pinfunction "VSSAON_AC3") (pintype "passive"))
      (node (ref "U1") (pin "AC5") (pinfunction "VSSA_AC5") (pintype "passive"))
      (node (ref "U1") (pin "AF6") (pinfunction "VREFN_AF6") (pintype "passive"))
      (node (ref "U1") (pin "AG1") (pinfunction "VSS_AG1") (pintype "passive"))
      (node (ref "U1") (pin "AG27") (pinfunction "VSS_AG27") (pintype "passive"))
      (node (ref "U1") (pin "C10") (pinfunction "VSS_C10") (pintype "passive"))
      (node (ref "U1") (pin "C6") (pinfunction "VSS_C6") (pintype "passive"))
      (node (ref "U1") (pin "E7") (pinfunction "VSS_E7") (pintype "passive"))
      (node (ref "U1") (pin "F12") (pinfunction "VSS_F12") (pintype "passive"))
      (node (ref "U1") (pin "F14") (pinfunction "VSS_F14") (pintype "passive"))
      (node (ref "U1") (pin "F16") (pinfunction "VSS_F16") (pintype "passive"))
      (node (ref "U1") (pin "F3") (pinfunction "VSS_F3") (pintype "passive"))
      (node (ref "U1") (pin "J7") (pinfunction "VSS_J7") (pintype "passive"))
      (node (ref "U1") (pin "K3") (pinfunction "VSS_K3") (pintype "passive"))
      (node (ref "U1") (pin "V6") (pinfunction "VSS_V6") (pintype "passive"))
      (node (ref "U1") (pin "Y4") (pinfunction "VSS_Y4") (pintype "passive"))
    )
    (net (code "3") (name "Net-(C88-Pad2)") (class "Default")
      (node (ref "C88") (pin "2") (pinfunction "2_2") (pintype "passive"))
      (node (ref "D6") (pin "2") (pinfunction "2_2") (pintype "passive"))
      (node (ref "R66") (pin "2") (pinfunction "2_2") (pintype "passive"))
    )
    (net (code "4") (name "Net-(CN12-Pad1)") (class "Default")
      (node (ref "CN12") (pin "1") (pinfunction "1_1") (pintype "passive"))
      (node (ref "R66") (pin "1") (pinfunction "1_1") (pintype "passive"))
    )
    (net (code "5") (name "Net-(D6-Pad1)") (class "Default")
      (node (ref "D6") (pin "1") (pinfunction "1_1") (pintype "passive"))
      (node (ref "R67") (pin "1") (pinfunction "1_1") (pintype "passive"))
    )
    (net (code "6") (name "Net-(U1G-V08CAP)") (class "Default")
      (node (ref "C225") (pin "2") (pinfunction "2_2") (pintype "passive"))
      (node (ref "U1") (pin "R7") (pinfunction "V08CAP_R7") (pintype "passive"))
    )
    (net (code "7") (name "Net-(U1G-VDD33UCPD)") (class "Default")
      (node (ref "C251") (pin "2") (pinfunction "2_2") (pintype "passive"))
      (node (ref "R286") (pin "2") (pinfunction "2_2") (pintype "passive"))
      (node (ref "U1") (pin "AE21") (pinfunction "VDD33USB_AE21") (pintype "passive"))
      (node (ref "U1") (pin "AE22") (pinfunction "VDD33UCPD_AE22") (pintype "passive"))
    )
    (net (code "8") (name "Net-(U1G-VDDA18ADC)") (class "Default")
      (node (ref "C235") (pin "2") (pinfunction "2_2") (pintype "passive"))
      (node (ref "C244") (pin "2") (pinfunction "2_2") (pintype "passive"))
      (node (ref "R267") (pin "1") (pinfunction "1_1") (pintype "passive"))
      (node (ref "U1") (pin "AB6") (pinfunction "VDDA18ADC_AB6") (pintype "passive"))
    )
    (net (code "9") (name "Net-(U1G-VDDCOMBOPHY)") (class "Default")
      (node (ref "C151") (pin "2") (pinfunction "2_2") (pintype "passive"))
      (node (ref "C252") (pin "2") (pinfunction "2_2") (pintype "passive"))
      (node (ref "C260") (pin "2") (pinfunction "2_2") (pintype "passive"))
      (node (ref "R11") (pin "2") (pinfunction "2_2") (pintype "passive"))
      (node (ref "U1") (pin "AB20") (pinfunction "VDDCOMBOPHY_AB20") (pintype "passive"))
      (node (ref "U1") (pin "AB22") (pinfunction "VDDCOMBOPHYTX_AB22") (pintype "passive"))
      (node (ref "U1") (pin "AC21") (pinfunction "VDDPCIECLK_AC21") (pintype "passive"))
    )
    (net (code "10") (name "VBAT") (class "Default")
      (node (ref "C87") (pin "2") (pinfunction "2_2") (pintype "passive"))
      (node (ref "D6") (pin "3") (pinfunction "3_3") (pintype "passive"))
      (node (ref "U1") (pin "T6") (pinfunction "VBAT_T6") (pintype "passive"))
    )
    (net (code "11") (name "VDD3V3_USB") (class "Default")
      (node (ref "R286") (pin "1") (pinfunction "1_1") (pintype "passive"))
    )
    (net (code "12") (name "VDDA1V8_AON") (class "Default")
      (node (ref "C234") (pin "2") (pinfunction "2_2") (pintype "passive"))
      (node (ref "U1") (pin "AB3") (pinfunction "VDDA18AON_AB3") (pintype "passive"))
    )
    (net (code "13") (name "VDDCORE") (class "Default")
      (node (ref "C192") (pin "2") (pinfunction "2_2") (pintype "passive"))
      (node (ref "C197") (pin "2") (pinfunction "2_2") (pintype "passive"))
      (node (ref "C201") (pin "2") (pinfunction "2_2") (pintype "passive"))
      (node (ref "C44") (pin "1") (pinfunction "1_1") (pintype "passive"))
      (node (ref "C45") (pin "2") (pinfunction "2_2") (pintype "passive"))
      (node (ref "C46") (pin "2") (pinfunction "2_2") (pintype "passive"))
      (node (ref "C47") (pin "1") (pinfunction "1_1") (pintype "passive"))
      (node (ref "C48") (pin "2") (pinfunction "2_2") (pintype "passive"))
      (node (ref "C49") (pin "2") (pinfunction "2_2") (pintype "passive"))
      (node (ref "C50") (pin "2") (pinfunction "2_2") (pintype "passive"))
      (node (ref "C51") (pin "2") (pinfunction "2_2") (pintype "passive"))
      (node (ref "R11") (pin "1") (pinfunction "1_1") (pintype "passive"))
      (node (ref "U1") (pin "1C1") (pinfunction "VDDCORE_1C1") (pintype "passive"))
      (node (ref "U1") (pin "1C3") (pinfunction "VDDCORE_1C3") (pintype "passive"))
      (node (ref "U1") (pin "1C5") (pinfunction "VDDCORE_1C5") (pintype "passive"))
      (node (ref "U1") (pin "1D2") (pinfunction "VDDCORE_1D2") (pintype "passive"))
      (node (ref "U1") (pin "1D4") (pinfunction "VDDCORE_1D4") (pintype "passive"))
      (node (ref "U1") (pin "1E3") (pinfunction "VDDCORE_1E3") (pintype "passive"))
      (node (ref "U1") (pin "1E5") (pinfunction "VDDCORE_1E5") (pintype "passive"))
      (node (ref "U1") (pin "1F2") (pinfunction "VDDCORE_1F2") (pintype "passive"))
      (node (ref "U1") (pin "1F4") (pinfunction "VDDCORE_1F4") (pintype "passive"))
      (node (ref "U1") (pin "E5") (pinfunction "VDDCSI_E5") (pintype "passive"))
      (node (ref "U1") (pin "F4") (pinfunction "VDDLVDS_F4") (pintype "passive"))
      (node (ref "U1") (pin "F8") (pinfunction "VDDDSI_F8") (pintype "passive"))
    )
    (net (code "14") (name "VDDCPU") (class "Default")
      (node (ref "C62") (pin "1") (pinfunction "1_1") (pintype "passive"))
      (node (ref "C63") (pin "2") (pinfunction "2_2") (pintype "passive"))
      (node (ref "C64") (pin "2") (pinfunction "2_2") (pintype "passive"))
      (node (ref "C65") (pin "1") (pinfunction "1_1") (pintype "passive"))
      (node (ref "C66") (pin "2") (pinfunction "2_2") (pintype "passive"))
      (node (ref "C67") (pin "2") (pinfunction "2_2") (pintype "passive"))
      (node (ref "C68") (pin "2") (pinfunction "2_2") (pintype "passive"))
      (node (ref "C69") (pin "2") (pinfunction "2_2") (pintype "passive"))
      (node (ref "U1") (pin "1C7") (pinfunction "VDDCPU_1C7") (pintype "passive"))
      (node (ref "U1") (pin "1C9") (pinfunction "VDDCPU_1C9") (pintype "passive"))
      (node (ref "U1") (pin "1D10") (pinfunction "VDDCPU_1D10") (pintype "passive"))
      (node (ref "U1") (pin "1D6") (pinfunction "VDDCPU_1D6") (pintype "passive"))
      (node (ref "U1") (pin "1D8") (pinfunction "VDDCPU_1D8") (pintype "passive"))
      (node (ref "U1") (pin "F18") (pinfunction "VDDCPU_F18") (pintype "passive"))
      (node (ref "U1") (pin "G15") (pinfunction "VDDCPU_G15") (pintype "passive"))
      (node (ref "U1") (pin "G17") (pinfunction "VDDCPU_G17") (pintype "passive"))
    )
    (net (code "15") (name "VDDGPU") (class "Default")
      (node (ref "C52") (pin "2") (pinfunction "2_2") (pintype "passive"))
      (node (ref "C53") (pin "2") (pinfunction "2_2") (pintype "passive"))
      (node (ref "C54") (pin "2") (pinfunction "2_2") (pintype "passive"))
      (node (ref "C55") (pin "2") (pinfunction "2_2") (pintype "passive"))
      (node (ref "C57") (pin "2") (pinfunction "2_2") (pintype "passive"))
      (node (ref "C58") (pin "2") (pinfunction "2_2") (pintype "passive"))
      (node (ref "C59") (pin "2") (pinfunction "2_2") (pintype "passive"))
      (node (ref "C60") (pin "2") (pinfunction "2_2") (pintype "passive"))
      (node (ref "U1") (pin "1G7") (pinfunction "VDDGPU_1G7") (pintype "passive"))
      (node (ref "U1") (pin "1G9") (pinfunction "VDDGPU_1G9") (pintype "passive"))
      (node (ref "U1") (pin "1H10") (pinfunction "VDDGPU_1H10") (pintype "passive"))
      (node (ref "U1") (pin "1H6") (pinfunction "VDDGPU_1H6") (pintype "passive"))
      (node (ref "U1") (pin "1H8") (pinfunction "VDDGPU_1H8") (pintype "passive"))
      (node (ref "U1") (pin "1L7") (pinfunction "VDDGPU_1L7") (pintype "passive"))
      (node (ref "U1") (pin "1L9") (pinfunction "VDDGPU_1L9") (pintype "passive"))
      (node (ref "U1") (pin "1M10") (pinfunction "VDDGPU_1M10") (pintype "passive"))
      (node (ref "U1") (pin "1M6") (pinfunction "VDDGPU_1M6") (pintype "passive"))
      (node (ref "U1") (pin "1M8") (pinfunction "VDDGPU_1M8") (pintype "passive"))
    )
    (net (code "16") (name "VDDIO") (class "Default")
      (node (ref "C196") (pin "2") (pinfunction "2_2") (pintype "passive"))
      (node (ref "C205") (pin "2") (pinfunction "2_2") (pintype "passive"))
      (node (ref "C70") (pin "1") (pinfunction "1_1") (pintype "passive"))
      (node (ref "C71") (pin "2") (pinfunction "2_2") (pintype "passive"))
      (node (ref "C72") (pin "2") (pinfunction "2_2") (pintype "passive"))
      (node (ref "C73") (pin "1") (pinfunction "1_1") (pintype "passive"))
      (node (ref "C74") (pin "2") (pinfunction "2_2") (pintype "passive"))
      (node (ref "R67") (pin "2") (pinfunction "2_2") (pintype "passive"))
      (node (ref "U1") (pin "1L1") (pinfunction "VDD_1L1") (pintype "passive"))
      (node (ref "U1") (pin "1L3") (pinfunction "VDD_1L3") (pintype "passive"))
      (node (ref "U1") (pin "1L5") (pinfunction "VDD_1L5") (pintype "passive"))
      (node (ref "U1") (pin "1M2") (pinfunction "VDD_1M2") (pintype "passive"))
      (node (ref "U1") (pin "1M4") (pinfunction "VDD_1M4") (pintype "passive"))
      (node (ref "U1") (pin "D10") (pinfunction "VDDIO3_D10") (pintype "passive"))
      (node (ref "U1") (pin "E11") (pinfunction "VDDIO3_E11") (pintype "passive"))
      (node (ref "U1") (pin "E9") (pinfunction "VDDIO4_E9") (pintype "passive"))
      (node (ref "U1") (pin "G11") (pinfunction "VDDIO4_G11") (pintype "passive"))
    )
    (net (code "17") (name "VDDIO_SDCARD") (class "Default")
      (node (ref "C195") (pin "2") (pinfunction "2_2") (pintype "passive"))
      (node (ref "U1") (pin "D14") (pinfunction "VDDIO1_D14") (pintype "passive"))
      (node (ref "U1") (pin "E13") (pinfunction "VDDIO1_E13") (pintype "passive"))
    )
    (net (code "18") (name "VDD_DDR") (class "Default")
      (node (ref "C75") (pin "2") (pinfunction "2_2") (pintype "passive"))
      (node (ref "C76") (pin "2") (pinfunction "2_2") (pintype "passive"))
      (node (ref "C77") (pin "1") (pinfunction "1_1") (pintype "passive"))
      (node (ref "C82") (pin "2") (pinfunction "2_2") (pintype "passive"))
      (node (ref "C83") (pin "2") (pinfunction "2_2") (pintype "passive"))
      (node (ref "U1") (pin "1C11") (pinfunction "VDDQDDR_1C11") (pintype "passive"))
      (node (ref "U1") (pin "1D12") (pinfunction "VDDQDDR_1D12") (pintype "passive"))
      (node (ref "U1") (pin "1E11") (pinfunction "VDDQDDR_1E11") (pintype "passive"))
      (node (ref "U1") (pin "1F12") (pinfunction "VDDQDDR_1F12") (pintype "passive"))
      (node (ref "U1") (pin "1L11") (pinfunction "VDDQDDR_1L11") (pintype "passive"))
      (node (ref "U1") (pin "1M12") (pinfunction "VDDQDDR_1M12") (pintype "passive"))
      (node (ref "U1") (pin "M22") (pinfunction "VDDQDDR_M22") (pintype "passive"))
      (node (ref "U1") (pin "N21") (pinfunction "VDDQDDR_N21") (pintype "passive"))
      (node (ref "U1") (pin "R21") (pinfunction "VDDQDDR_R21") (pintype "passive"))
    )
    (net (code "19") (name "VREF+") (class "Default")
      (node (ref "C248") (pin "2") (pinfunction "2_2") (pintype "passive"))
      (node (ref "C250") (pin "2") (pinfunction "2_2") (pintype "passive"))
      (node (ref "R269") (pin "2") (pinfunction "2_2") (pintype "passive"))
      (node (ref "U1") (pin "AG6") (pinfunction "VREFP_AG6") (pintype "passive"))
    )
  )
)
